# MINIPC_Board.net
KiCad netlist of a schematic drawn in EasyEDA Pro
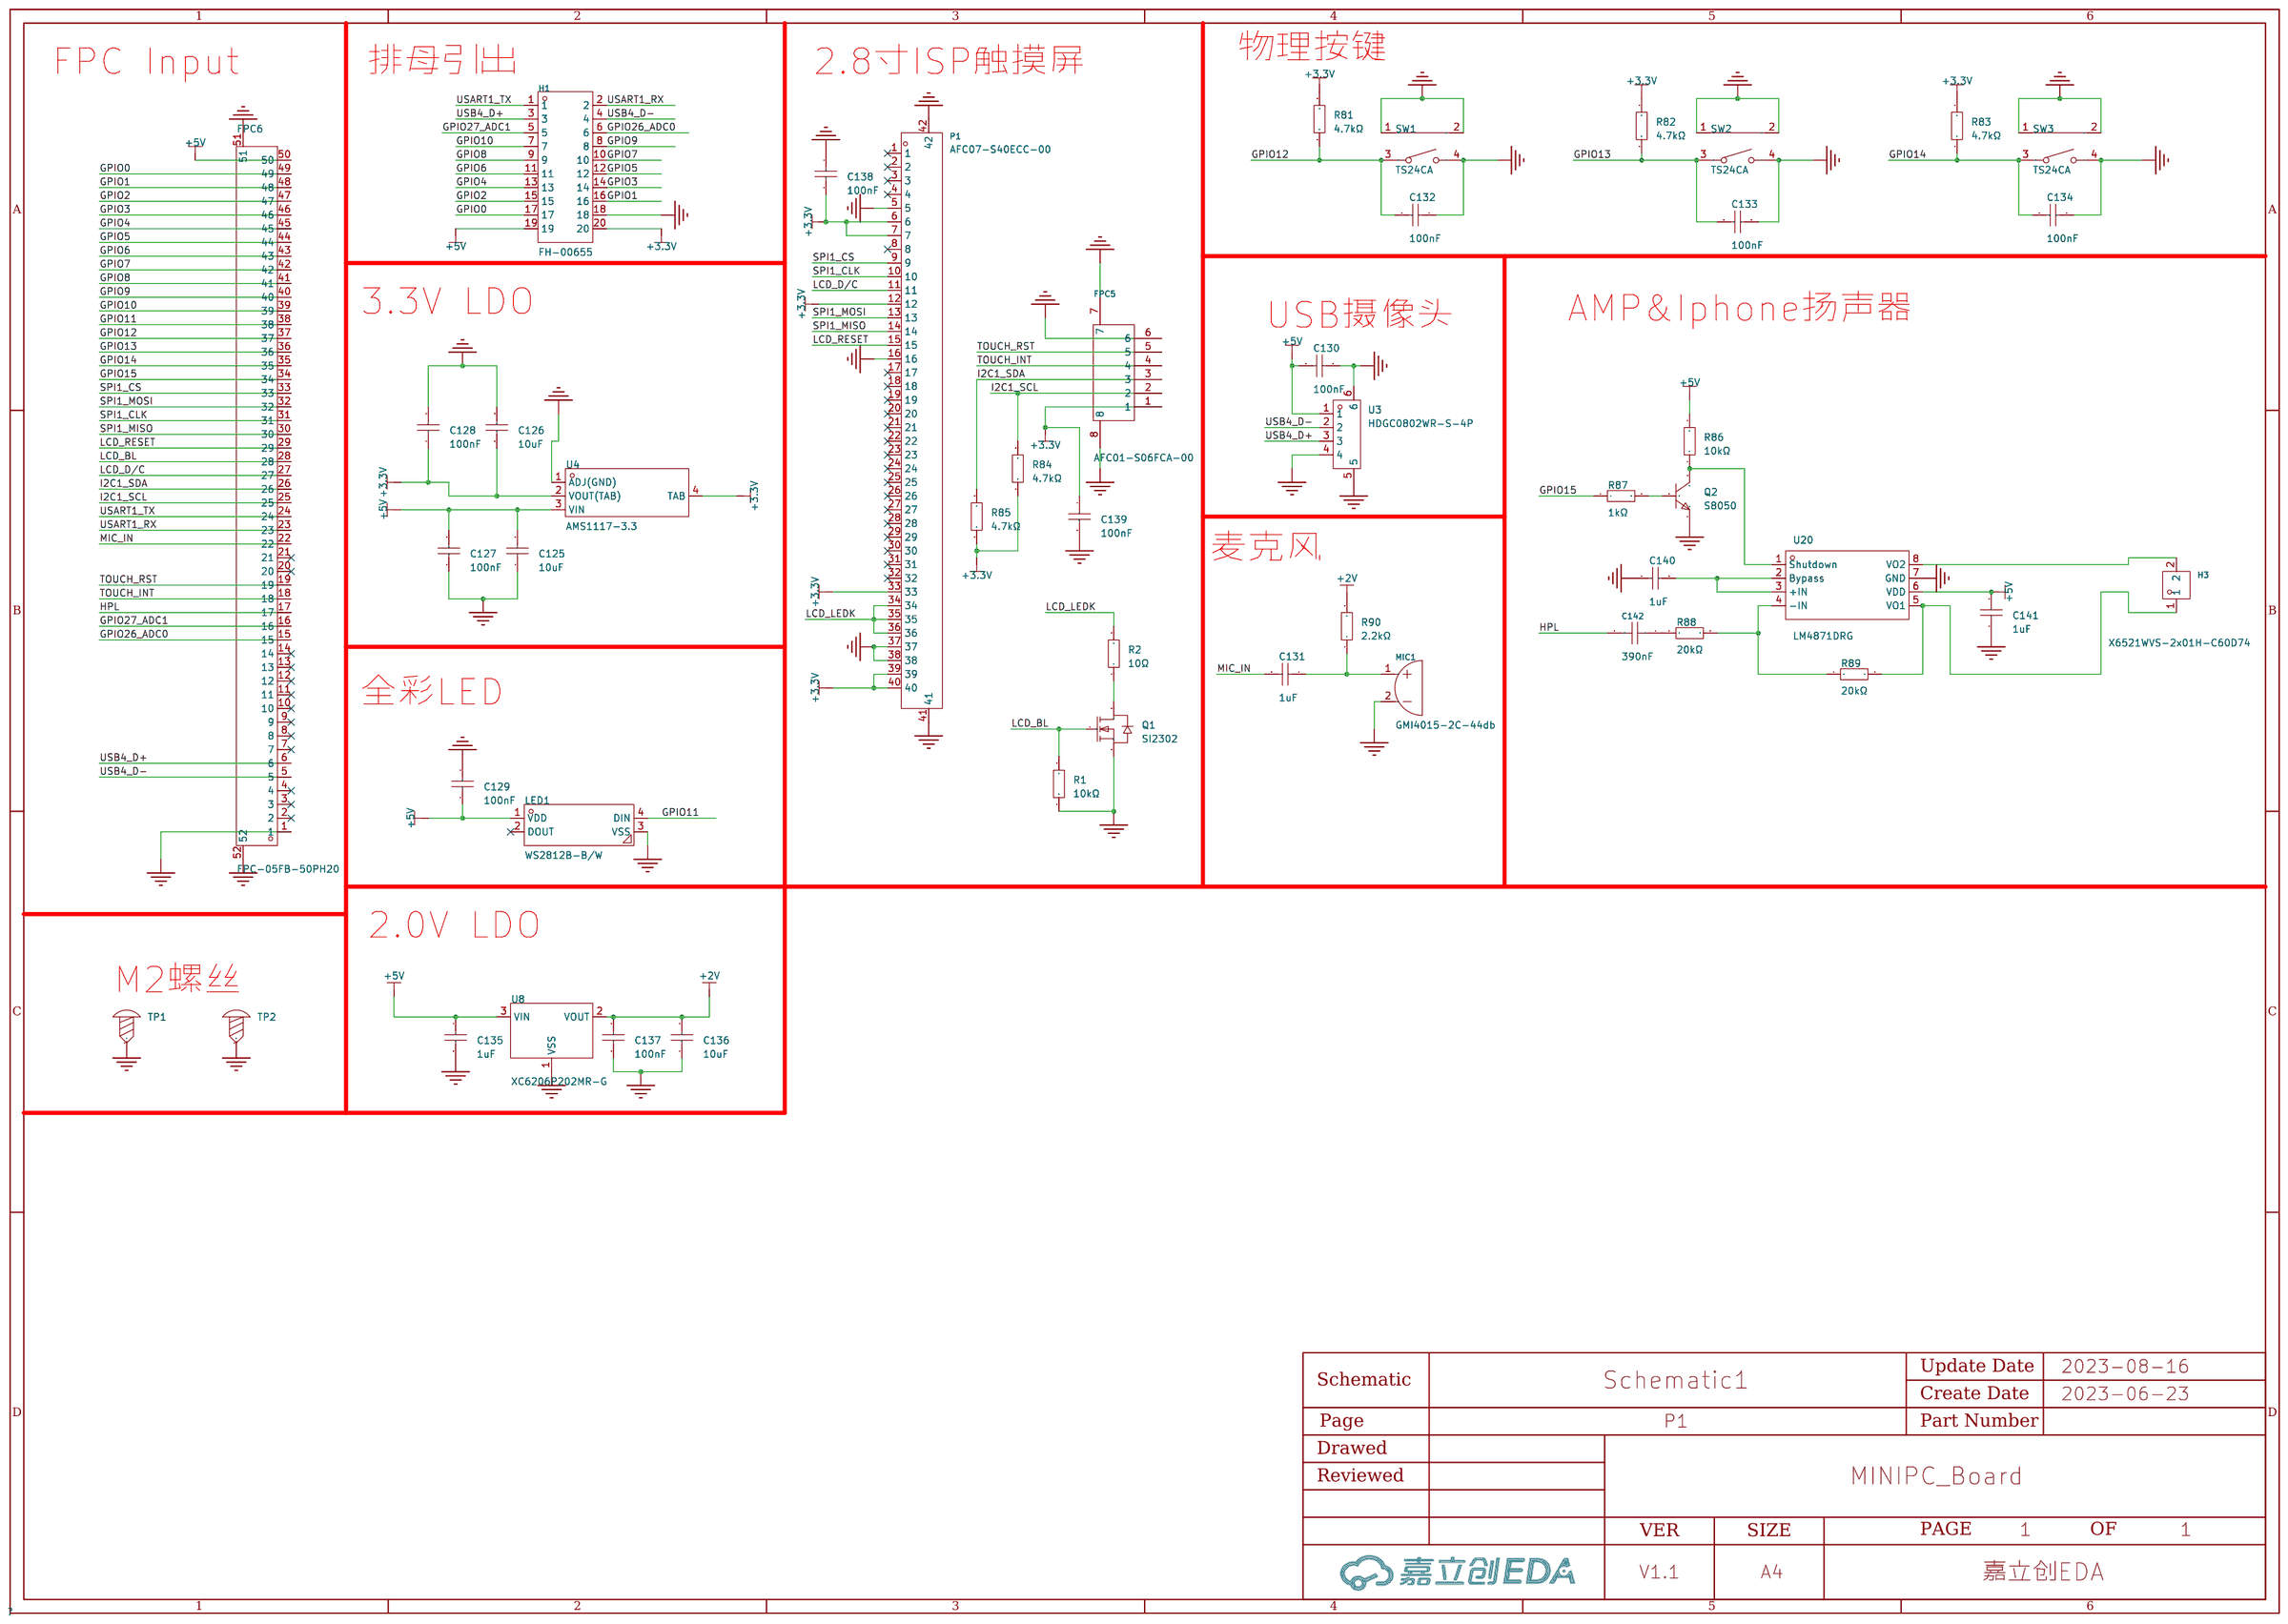
[diagram p0: schematic sheet]

(export (version "E")
  (design (tool "Eeschema 10.0.6"))
  (components
    (comp (ref "C125")
      (value "10uF")
      (footprint "easyedapro:C0805")
      (description "容值:10uF;精度:±10%;额定电压:25V;材质(温度系数):X5R;")
      (fields
        (field (name "Manufacturer Part") "CL21A106KAYNNNE")
        (field (name "Manufacturer") "SAMSUNG(三星)")
      )
      (libsource (lib "easyedapro") (part "CL21A106KAYNNNE"))
    )
    (comp (ref "C126")
      (value "10uF")
      (footprint "easyedapro:C0805")
      (description "容值:10uF;精度:±10%;额定电压:25V;材质(温度系数):X5R;")
      (fields
        (field (name "Manufacturer Part") "CL21A106KAYNNNE")
        (field (name "Manufacturer") "SAMSUNG(三星)")
      )
      (libsource (lib "easyedapro") (part "CL21A106KAYNNNE"))
    )
    (comp (ref "C127")
      (value "100nF")
      (footprint "easyedapro:C0805")
      (description "容值:100nF;精度:±10%;额定电压:50V;材质(温度系数):X7R;")
      (fields (field (name "Manufacturer Part") "0805B104K500NT") (field (name "Manufacturer") "FH(风华)"))
      (libsource (lib "easyedapro") (part "0805B104K500NT"))
    )
    (comp (ref "C128")
      (value "100nF")
      (footprint "easyedapro:C0805")
      (description "容值:100nF;精度:±10%;额定电压:50V;材质(温度系数):X7R;")
      (fields (field (name "Manufacturer Part") "0805B104K500NT") (field (name "Manufacturer") "FH(风华)"))
      (libsource (lib "easyedapro") (part "0805B104K500NT"))
    )
    (comp (ref "C129")
      (value "100nF")
      (footprint "easyedapro:C0805")
      (description "容值:100nF;精度:±10%;额定电压:50V;材质(温度系数):X7R;")
      (fields (field (name "Manufacturer Part") "0805B104K500NT") (field (name "Manufacturer") "FH(风华)"))
      (libsource (lib "easyedapro") (part "0805B104K500NT"))
    )
    (comp (ref "C130")
      (value "100nF")
      (footprint "easyedapro:C0805")
      (description "容值:100nF;精度:±10%;额定电压:50V;材质(温度系数):X7R;")
      (fields (field (name "Manufacturer Part") "0805B104K500NT") (field (name "Manufacturer") "FH(风华)"))
      (libsource (lib "easyedapro") (part "0805B104K500NT"))
    )
    (comp (ref "C131")
      (value "1uF")
      (footprint "easyedapro:C0805")
      (description "容值:1uF;精度:±10%;额定电压:50V;材质(温度系数):X7R;")
      (fields
        (field (name "Manufacturer Part") "CL21B105KBFNNNE")
        (field (name "Manufacturer") "SAMSUNG(三星)")
      )
      (libsource (lib "easyedapro") (part "CL21B105KBFNNNE"))
    )
    (comp (ref "C132")
      (value "100nF")
      (footprint "easyedapro:C0805")
      (description "容值:100nF;精度:±10%;额定电压:50V;材质(温度系数):X7R;")
      (fields (field (name "Manufacturer Part") "0805B104K500NT") (field (name "Manufacturer") "FH(风华)"))
      (libsource (lib "easyedapro") (part "0805B104K500NT"))
    )
    (comp (ref "C133")
      (value "100nF")
      (footprint "easyedapro:C0805")
      (description "容值:100nF;精度:±10%;额定电压:50V;材质(温度系数):X7R;")
      (fields (field (name "Manufacturer Part") "0805B104K500NT") (field (name "Manufacturer") "FH(风华)"))
      (libsource (lib "easyedapro") (part "0805B104K500NT"))
    )
    (comp (ref "C134")
      (value "100nF")
      (footprint "easyedapro:C0805")
      (description "容值:100nF;精度:±10%;额定电压:50V;材质(温度系数):X7R;")
      (fields (field (name "Manufacturer Part") "0805B104K500NT") (field (name "Manufacturer") "FH(风华)"))
      (libsource (lib "easyedapro") (part "0805B104K500NT"))
    )
    (comp (ref "C135")
      (value "1uF")
      (footprint "easyedapro:C0805")
      (description "容值:1uF;精度:±10%;额定电压:50V;材质(温度系数):X7R;")
      (fields
        (field (name "Manufacturer Part") "CL21B105KBFNNNE")
        (field (name "Manufacturer") "SAMSUNG(三星)")
      )
      (libsource (lib "easyedapro") (part "CL21B105KBFNNNE"))
    )
    (comp (ref "C136")
      (value "10uF")
      (footprint "easyedapro:C0805")
      (description "容值:10uF;精度:±10%;额定电压:25V;材质(温度系数):X5R;")
      (fields
        (field (name "Manufacturer Part") "CL21A106KAYNNNE")
        (field (name "Manufacturer") "SAMSUNG(三星)")
      )
      (libsource (lib "easyedapro") (part "CL21A106KAYNNNE"))
    )
    (comp (ref "C137")
      (value "100nF")
      (footprint "easyedapro:C0805")
      (description "容值:100nF;精度:±10%;额定电压:50V;材质(温度系数):X7R;")
      (fields (field (name "Manufacturer Part") "0805B104K500NT") (field (name "Manufacturer") "FH(风华)"))
      (libsource (lib "easyedapro") (part "0805B104K500NT"))
    )
    (comp (ref "C138")
      (value "100nF")
      (footprint "easyedapro:C0805")
      (description "容值:100nF;精度:±10%;额定电压:50V;材质(温度系数):X7R;")
      (fields (field (name "Manufacturer Part") "0805B104K500NT") (field (name "Manufacturer") "FH(风华)"))
      (libsource (lib "easyedapro") (part "0805B104K500NT"))
    )
    (comp (ref "C139")
      (value "100nF")
      (footprint "easyedapro:C0805")
      (description "容值:100nF;精度:±10%;额定电压:50V;材质(温度系数):X7R;")
      (fields (field (name "Manufacturer Part") "0805B104K500NT") (field (name "Manufacturer") "FH(风华)"))
      (libsource (lib "easyedapro") (part "0805B104K500NT"))
    )
    (comp (ref "C140")
      (value "1uF")
      (footprint "easyedapro:C0805")
      (description "容值:1uF;精度:±10%;额定电压:50V;材质(温度系数):X7R;")
      (fields
        (field (name "Manufacturer Part") "CL21B105KBFNNNE")
        (field (name "Manufacturer") "SAMSUNG(三星)")
      )
      (libsource (lib "easyedapro") (part "CL21B105KBFNNNE"))
    )
    (comp (ref "C141")
      (value "1uF")
      (footprint "easyedapro:C0805")
      (description "容值:1uF;精度:±10%;额定电压:50V;材质(温度系数):X7R;")
      (fields
        (field (name "Manufacturer Part") "CL21B105KBFNNNE")
        (field (name "Manufacturer") "SAMSUNG(三星)")
      )
      (libsource (lib "easyedapro") (part "CL21B105KBFNNNE"))
    )
    (comp (ref "C142")
      (value "390nF")
      (footprint "easyedapro:C0805")
      (description "容值:390nF;精度:±10%;额定电压:50V;材质(温度系数):X7R;")
      (fields (field (name "Manufacturer Part") "0805B394K500CT") (field (name "Manufacturer") "Walsin(华新科)"))
      (libsource (lib "easyedapro") (part "0805B394K500CT"))
    )
    (comp (ref "FPC5")
      (value "AFC01-S06FCA-00")
      (footprint "easyedapro:FPC-SMD_P0.50-6P_AFC01-S06FCA-00")
      (description "间距:0.5mm;触点数量:6;锁定特性:翻盖式;安装类型:卧贴;触点类型:下接;")
      (fields (field (name "Manufacturer") "JS(钜硕电子)"))
      (libsource (lib "easyedapro") (part "AFC01-S06FCA-00"))
    )
    (comp (ref "FPC6")
      (value "FPC-05FB-50PH20")
      (footprint "easyedapro:FPC-SMD_50P-P0.50_FPC-05FB-50PH20")
      (fields (field (name "Manufacturer") "XUNPU(讯普)"))
      (libsource (lib "easyedapro") (part "FPC-05FB-50PH20"))
    )
    (comp (ref "H1")
      (value "FH-00655")
      (footprint "easyedapro:HDR-SMD_20P-P2.54-V-F-R2-C10-S2.54-LS7.2-1")
      (fields (field (name "Manufacturer") "Liansheng(连盛)"))
      (libsource (lib "easyedapro") (part "FH-00655"))
    )
    (comp (ref "H3")
      (value "X6521WVS-2x01H-C60D74")
      (footprint "easyedapro:HDR-SMD_2P-P2.54-V-M-R2-C1-LS7.4")
      (fields (field (name "Manufacturer") "XKB Connectivity(中国星坤)"))
      (libsource (lib "easyedapro") (part "X6521WVS-2X01H-C60D74"))
    )
    (comp (ref "LED1")
      (value "WS2812B-B/W")
      (footprint "easyedapro:LED-SMD_4P-L5.0-W5.0-BL_TC5050RGB")
      (description "发光颜色:RGB三色;")
      (fields (field (name "Manufacturer") "worldsemi"))
      (libsource (lib "easyedapro") (part "WS2812B-B"))
    )
    (comp (ref "MIC1")
      (value "GMI4015-2C-44db")
      (footprint "easyedapro:MIC-SMD_BD4.0_GMI4015-2C-32DB")
      (fields (field (name "Manufacturer") "INGHAi(赢海)"))
      (libsource (lib "easyedapro") (part "GMI4015-2C-44DB"))
    )
    (comp (ref "P1")
      (value "AFC07-S40ECC-00")
      (footprint "easyedapro:CONN-SMD_AFC07-S40ECC-00")
      (description "间距:0.5mm;触点数量:40P;锁定特性:抽屉式;安装类型:卧贴;触点类型:上接;")
      (fields (field (name "Manufacturer") "JS(钜硕电子)"))
      (libsource (lib "easyedapro") (part "FPC 0.5MM 40P Pull type H2.0mm Pick up"))
    )
    (comp (ref "Q1")
      (value "SI2302")
      (footprint "easyedapro:SOT-23-3_L2.9-W1.5-P1.90-LS2.6-BL")
      (fields (field (name "Manufacturer") "TWGMC(台湾迪嘉)"))
      (libsource (lib "easyedapro") (part "SI2302_C727152"))
    )
    (comp (ref "Q2")
      (value "S8050")
      (footprint "easyedapro:SOT-23-3_L2.9-W1.6-P1.90-LS2.8-BR")
      (description "晶体管类型:NPN;集射极击穿电压(Vceo):25V;集电极电流(Ic):500mA;功率(Pd):300mW;直流电流增益(hFE@Ic,Vce):120@50mA,1V;")
      (fields (field (name "Manufacturer") "CJ(江苏长电/长晶)"))
      (libsource (lib "easyedapro") (part "S8050_C105433"))
    )
    (comp (ref "R1")
      (value "10kΩ")
      (footprint "easyedapro:R0805")
      (description "电阻类型:厚膜电阻;阻值:10kΩ;精度:±1%;功率:125mW;")
      (fields
        (field (name "Manufacturer Part") "0805W8F1002T5E")
        (field (name "Manufacturer") "UNI-ROYAL(厚声)")
      )
      (libsource (lib "easyedapro") (part "0805W8F1002T5E"))
    )
    (comp (ref "R2")
      (value "10Ω")
      (footprint "easyedapro:R0805_NEW")
      (description "电阻类型:厚膜电阻;阻值:10Ω;精度:±1%;功率:125mW;")
      (fields
        (field (name "Manufacturer Part") "0805W8F100JT5E")
        (field (name "Manufacturer") "UNI-ROYAL(厚声)")
      )
      (libsource (lib "easyedapro") (part "0805W8F100JT5E"))
    )
    (comp (ref "R81")
      (value "4.7kΩ")
      (footprint "easyedapro:R0805")
      (description "电阻类型:厚膜电阻;阻值:4.7kΩ;精度:±1%;功率:125mW;")
      (fields
        (field (name "Manufacturer Part") "0805W8F4701T5E")
        (field (name "Manufacturer") "UNI-ROYAL(厚声)")
      )
      (libsource (lib "easyedapro") (part "0805W8F4701T5E"))
    )
    (comp (ref "R82")
      (value "4.7kΩ")
      (footprint "easyedapro:R0805")
      (description "电阻类型:厚膜电阻;阻值:4.7kΩ;精度:±1%;功率:125mW;")
      (fields
        (field (name "Manufacturer Part") "0805W8F4701T5E")
        (field (name "Manufacturer") "UNI-ROYAL(厚声)")
      )
      (libsource (lib "easyedapro") (part "0805W8F4701T5E"))
    )
    (comp (ref "R83")
      (value "4.7kΩ")
      (footprint "easyedapro:R0805")
      (description "电阻类型:厚膜电阻;阻值:4.7kΩ;精度:±1%;功率:125mW;")
      (fields
        (field (name "Manufacturer Part") "0805W8F4701T5E")
        (field (name "Manufacturer") "UNI-ROYAL(厚声)")
      )
      (libsource (lib "easyedapro") (part "0805W8F4701T5E"))
    )
    (comp (ref "R84")
      (value "4.7kΩ")
      (footprint "easyedapro:R0805")
      (description "电阻类型:厚膜电阻;阻值:4.7kΩ;精度:±1%;功率:125mW;")
      (fields
        (field (name "Manufacturer Part") "0805W8F4701T5E")
        (field (name "Manufacturer") "UNI-ROYAL(厚声)")
      )
      (libsource (lib "easyedapro") (part "0805W8F4701T5E"))
    )
    (comp (ref "R85")
      (value "4.7kΩ")
      (footprint "easyedapro:R0805")
      (description "电阻类型:厚膜电阻;阻值:4.7kΩ;精度:±1%;功率:125mW;")
      (fields
        (field (name "Manufacturer Part") "0805W8F4701T5E")
        (field (name "Manufacturer") "UNI-ROYAL(厚声)")
      )
      (libsource (lib "easyedapro") (part "0805W8F4701T5E"))
    )
    (comp (ref "R86")
      (value "10kΩ")
      (footprint "easyedapro:R0805")
      (description "电阻类型:厚膜电阻;阻值:10kΩ;精度:±1%;功率:125mW;")
      (fields
        (field (name "Manufacturer Part") "0805W8F1002T5E")
        (field (name "Manufacturer") "UNI-ROYAL(厚声)")
      )
      (libsource (lib "easyedapro") (part "0805W8F1002T5E"))
    )
    (comp (ref "R87")
      (value "1kΩ")
      (footprint "easyedapro:R0805")
      (description "电阻类型:厚膜电阻;阻值:1kΩ;精度:±1%;功率:125mW;")
      (fields
        (field (name "Manufacturer Part") "0805W8F1001T5E")
        (field (name "Manufacturer") "UNI-ROYAL(厚声)")
      )
      (libsource (lib "easyedapro") (part "0805W8F1001T5E"))
    )
    (comp (ref "R88")
      (value "20kΩ")
      (footprint "easyedapro:R0805")
      (description "电阻类型:厚膜电阻;阻值:20kΩ;精度:±1%;功率:125mW;")
      (fields
        (field (name "Manufacturer Part") "0805W8F2002T5E")
        (field (name "Manufacturer") "UNI-ROYAL(厚声)")
      )
      (libsource (lib "easyedapro") (part "0805W8F2002T5E"))
    )
    (comp (ref "R89")
      (value "20kΩ")
      (footprint "easyedapro:R0805")
      (description "电阻类型:厚膜电阻;阻值:20kΩ;精度:±1%;功率:125mW;")
      (fields
        (field (name "Manufacturer Part") "0805W8F2002T5E")
        (field (name "Manufacturer") "UNI-ROYAL(厚声)")
      )
      (libsource (lib "easyedapro") (part "0805W8F2002T5E"))
    )
    (comp (ref "R90")
      (value "2.2kΩ")
      (footprint "easyedapro:R0805")
      (description "电阻类型:厚膜电阻;阻值:2.2kΩ;精度:±1%;功率:125mW;")
      (fields
        (field (name "Manufacturer Part") "0805W8F2201T5E")
        (field (name "Manufacturer") "UNI-ROYAL(厚声)")
      )
      (libsource (lib "easyedapro") (part "0805W8F2201T5E"))
    )
    (comp (ref "SW1")
      (value "TS24CA")
      (footprint "easyedapro:SW-SMD_TS24CA")
      (description "触点电流:50mA;额定电压(DC):12V;电路结构:单刀单掷;安装方式:卧贴;带灯:-;机械寿命:-;")
      (fields (field (name "Manufacturer") "SHOU HAN(首韩)"))
      (libsource (lib "easyedapro") (part "TS24CA"))
    )
    (comp (ref "SW2")
      (value "TS24CA")
      (footprint "easyedapro:SW-SMD_TS24CA")
      (description "触点电流:50mA;额定电压(DC):12V;电路结构:单刀单掷;安装方式:卧贴;带灯:-;机械寿命:-;")
      (fields (field (name "Manufacturer") "SHOU HAN(首韩)"))
      (libsource (lib "easyedapro") (part "TS24CA"))
    )
    (comp (ref "SW3")
      (value "TS24CA")
      (footprint "easyedapro:SW-SMD_TS24CA")
      (description "触点电流:50mA;额定电压(DC):12V;电路结构:单刀单掷;安装方式:卧贴;带灯:-;机械寿命:-;")
      (fields (field (name "Manufacturer") "SHOU HAN(首韩)"))
      (libsource (lib "easyedapro") (part "TS24CA"))
    )
    (comp (ref "TP1") (value "~") (footprint "easyedapro:M2螺丝") (libsource (lib "easyedapro") (part "螺丝孔")))
    (comp (ref "TP2") (value "~") (footprint "easyedapro:M2螺丝") (libsource (lib "easyedapro") (part "螺丝孔")))
    (comp (ref "U3")
      (value "HDGC0802WR-S-4P")
      (footprint "easyedapro:CONN-SMD_4P-P0.80_HDGC_HDGC0802WR-S-4P")
      (description "间距:0.8mm;插针结构:1x4P;排数:1;每排PIN数:4;公母:公型插针;安装方式:卧贴;工作温度范围:-25°C~+85°C;")
      (fields (field (name "Manufacturer") "HDGC(华德共创)"))
      (libsource (lib "easyedapro") (part "HDGC0802WR-S-4P"))
    )
    (comp (ref "U4")
      (value "AMS1117-3.3")
      (footprint "easyedapro:SOT-223-4_L6.5-W3.5-P2.30-LS7.0-BR")
      (description "输出类型:固定;输出极性:正;最大输入电压:18V;输出电压:3.3V;输出电流:1A;电源纹波抑制比(PSRR):60dB@(120Hz);")
      (fields (field (name "Manufacturer") "UMW(广东友台半导体)"))
      (libsource (lib "easyedapro") (part "AMS1117-3.3_C347222"))
    )
    (comp (ref "U8")
      (value "XC6206P202MR-G")
      (footprint "easyedapro:SOT-23-3_L3.0-W1.7-P0.95-LS2.9-BR")
      (description "输出类型:固定;输出极性:正;最大输入电压:8V;输出电压:3V;输出电流:300mA;")
      (fields (field (name "Manufacturer") "TOREX(特瑞仕)"))
      (libsource (lib "easyedapro") (part "XC6206P302MR_C5148691"))
    )
    (comp (ref "U20")
      (value "LM4871DRG")
      (footprint "easyedapro:SOP-8_L4.9-W3.9-P1.27-LS6.0-BL")
      (fields (field (name "Manufacturer") "HGC(深圳汉芯)"))
      (libsource (lib "easyedapro") (part "LM4871DRG"))
    )
  )
  (nets
    (net (code "1") (name "+2V") (class "Default")
      (node (ref "C136") (pin "2") (pinfunction "2_2") (pintype "input"))
      (node (ref "C137") (pin "2") (pinfunction "2_2") (pintype "input"))
      (node (ref "R90") (pin "2") (pinfunction "2_2") (pintype "input"))
      (node (ref "U8") (pin "2") (pinfunction "VOUT_2") (pintype "input"))
    )
    (net (code "2") (name "+3.3V") (class "Default")
      (node (ref "C126") (pin "1") (pinfunction "1_1") (pintype "input"))
      (node (ref "C128") (pin "1") (pinfunction "1_1") (pintype "input"))
      (node (ref "C138") (pin "2") (pinfunction "2_2") (pintype "input"))
      (node (ref "C139") (pin "1") (pinfunction "1_1") (pintype "input"))
      (node (ref "FPC5") (pin "1") (pinfunction "1_1") (pintype "input"))
      (node (ref "H1") (pin "20") (pinfunction "20_20") (pintype "input"))
      (node (ref "P1") (pin "12") (pinfunction "12_12") (pintype "input"))
      (node (ref "P1") (pin "33") (pinfunction "33_33") (pintype "input"))
      (node (ref "P1") (pin "39") (pinfunction "39_39") (pintype "input"))
      (node (ref "P1") (pin "40") (pinfunction "40_40") (pintype "input"))
      (node (ref "P1") (pin "6") (pinfunction "6_6") (pintype "input"))
      (node (ref "P1") (pin "7") (pinfunction "7_7") (pintype "input"))
      (node (ref "R81") (pin "2") (pinfunction "2_2") (pintype "input"))
      (node (ref "R82") (pin "2") (pinfunction "2_2") (pintype "input"))
      (node (ref "R83") (pin "2") (pinfunction "2_2") (pintype "input"))
      (node (ref "R84") (pin "1") (pinfunction "1_1") (pintype "input"))
      (node (ref "R85") (pin "1") (pinfunction "1_1") (pintype "input"))
      (node (ref "U4") (pin "2") (pinfunction "VOUT(TAB)_2") (pintype "input"))
      (node (ref "U4") (pin "4") (pinfunction "TAB_4") (pintype "input"))
    )
    (net (code "3") (name "+5V") (class "Default")
      (node (ref "C125") (pin "2") (pinfunction "2_2") (pintype "input"))
      (node (ref "C127") (pin "2") (pinfunction "2_2") (pintype "input"))
      (node (ref "C129") (pin "1") (pinfunction "1_1") (pintype "input"))
      (node (ref "C130") (pin "2") (pinfunction "2_2") (pintype "input"))
      (node (ref "C135") (pin "1") (pinfunction "1_1") (pintype "input"))
      (node (ref "C141") (pin "2") (pinfunction "2_2") (pintype "input"))
      (node (ref "FPC6") (pin "50") (pinfunction "50_50") (pintype "input"))
      (node (ref "H1") (pin "19") (pinfunction "19_19") (pintype "input"))
      (node (ref "LED1") (pin "1") (pinfunction "VDD_1") (pintype "input"))
      (node (ref "R86") (pin "2") (pinfunction "2_2") (pintype "input"))
      (node (ref "U20") (pin "6") (pinfunction "VDD_6") (pintype "input"))
      (node (ref "U3") (pin "1") (pinfunction "1_1") (pintype "input"))
      (node (ref "U4") (pin "3") (pinfunction "VIN_3") (pintype "input"))
      (node (ref "U8") (pin "3") (pinfunction "VIN_3") (pintype "input"))
    )
    (net (code "4") (name "/GPIO0") (class "Default")
      (node (ref "FPC6") (pin "49") (pinfunction "49_49") (pintype "input"))
      (node (ref "H1") (pin "17") (pinfunction "17_17") (pintype "input"))
    )
    (net (code "5") (name "/GPIO1") (class "Default")
      (node (ref "FPC6") (pin "48") (pinfunction "48_48") (pintype "input"))
      (node (ref "H1") (pin "16") (pinfunction "16_16") (pintype "input"))
    )
    (net (code "6") (name "/GPIO2") (class "Default")
      (node (ref "FPC6") (pin "47") (pinfunction "47_47") (pintype "input"))
      (node (ref "H1") (pin "15") (pinfunction "15_15") (pintype "input"))
    )
    (net (code "7") (name "/GPIO3") (class "Default")
      (node (ref "FPC6") (pin "46") (pinfunction "46_46") (pintype "input"))
      (node (ref "H1") (pin "14") (pinfunction "14_14") (pintype "input"))
    )
    (net (code "8") (name "/GPIO4") (class "Default")
      (node (ref "FPC6") (pin "45") (pinfunction "45_45") (pintype "input"))
      (node (ref "H1") (pin "13") (pinfunction "13_13") (pintype "input"))
    )
    (net (code "9") (name "/GPIO5") (class "Default")
      (node (ref "FPC6") (pin "44") (pinfunction "44_44") (pintype "input"))
      (node (ref "H1") (pin "12") (pinfunction "12_12") (pintype "input"))
    )
    (net (code "10") (name "/GPIO6") (class "Default")
      (node (ref "FPC6") (pin "43") (pinfunction "43_43") (pintype "input"))
      (node (ref "H1") (pin "11") (pinfunction "11_11") (pintype "input"))
    )
    (net (code "11") (name "/GPIO7") (class "Default")
      (node (ref "FPC6") (pin "42") (pinfunction "42_42") (pintype "input"))
      (node (ref "H1") (pin "10") (pinfunction "10_10") (pintype "input"))
    )
    (net (code "12") (name "/GPIO8") (class "Default")
      (node (ref "FPC6") (pin "41") (pinfunction "41_41") (pintype "input"))
      (node (ref "H1") (pin "9") (pinfunction "9_9") (pintype "input"))
    )
    (net (code "13") (name "/GPIO9") (class "Default")
      (node (ref "FPC6") (pin "40") (pinfunction "40_40") (pintype "input"))
      (node (ref "H1") (pin "8") (pinfunction "8_8") (pintype "input"))
    )
    (net (code "14") (name "/GPIO10") (class "Default")
      (node (ref "FPC6") (pin "39") (pinfunction "39_39") (pintype "input"))
      (node (ref "H1") (pin "7") (pinfunction "7_7") (pintype "input"))
    )
    (net (code "15") (name "/GPIO11") (class "Default")
      (node (ref "FPC6") (pin "38") (pinfunction "38_38") (pintype "input"))
      (node (ref "LED1") (pin "4") (pinfunction "DIN_4") (pintype "input"))
    )
    (net (code "16") (name "/GPIO12") (class "Default")
      (node (ref "C132") (pin "2") (pinfunction "2_2") (pintype "input"))
      (node (ref "FPC6") (pin "37") (pinfunction "37_37") (pintype "input"))
      (node (ref "R81") (pin "1") (pinfunction "1_1") (pintype "input"))
      (node (ref "SW1") (pin "3") (pinfunction "3_3") (pintype "input"))
    )
    (net (code "17") (name "/GPIO13") (class "Default")
      (node (ref "C133") (pin "2") (pinfunction "2_2") (pintype "input"))
      (node (ref "FPC6") (pin "36") (pinfunction "36_36") (pintype "input"))
      (node (ref "R82") (pin "1") (pinfunction "1_1") (pintype "input"))
      (node (ref "SW2") (pin "3") (pinfunction "3_3") (pintype "input"))
    )
    (net (code "18") (name "/GPIO14") (class "Default")
      (node (ref "C134") (pin "2") (pinfunction "2_2") (pintype "input"))
      (node (ref "FPC6") (pin "35") (pinfunction "35_35") (pintype "input"))
      (node (ref "R83") (pin "1") (pinfunction "1_1") (pintype "input"))
      (node (ref "SW3") (pin "3") (pinfunction "3_3") (pintype "input"))
    )
    (net (code "19") (name "/GPIO15") (class "Default")
      (node (ref "FPC6") (pin "34") (pinfunction "34_34") (pintype "input"))
      (node (ref "R87") (pin "1") (pinfunction "1_1") (pintype "input"))
    )
    (net (code "20") (name "/GPIO26_ADC0") (class "Default")
      (node (ref "FPC6") (pin "15") (pinfunction "15_15") (pintype "input"))
      (node (ref "H1") (pin "6") (pinfunction "6_6") (pintype "input"))
    )
    (net (code "21") (name "/GPIO27_ADC1") (class "Default")
      (node (ref "FPC6") (pin "16") (pinfunction "16_16") (pintype "input"))
      (node (ref "H1") (pin "5") (pinfunction "5_5") (pintype "input"))
    )
    (net (code "22") (name "/HPL") (class "Default")
      (node (ref "C142") (pin "2") (pinfunction "2_2") (pintype "input"))
      (node (ref "FPC6") (pin "17") (pinfunction "17_17") (pintype "input"))
    )
    (net (code "23") (name "/I2C1_SCL") (class "Default")
      (node (ref "FPC5") (pin "2") (pinfunction "2_2") (pintype "input"))
      (node (ref "FPC6") (pin "25") (pinfunction "25_25") (pintype "input"))
      (node (ref "R84") (pin "2") (pinfunction "2_2") (pintype "input"))
    )
    (net (code "24") (name "/I2C1_SDA") (class "Default")
      (node (ref "FPC5") (pin "3") (pinfunction "3_3") (pintype "input"))
      (node (ref "FPC6") (pin "26") (pinfunction "26_26") (pintype "input"))
      (node (ref "R85") (pin "2") (pinfunction "2_2") (pintype "input"))
    )
    (net (code "25") (name "/LCD_BL") (class "Default")
      (node (ref "FPC6") (pin "28") (pinfunction "28_28") (pintype "input"))
      (node (ref "Q1") (pin "1") (pinfunction "G_1") (pintype "input"))
      (node (ref "R1") (pin "2") (pinfunction "2_2") (pintype "input"))
    )
    (net (code "26") (name "/LCD_D{slash}C") (class "Default")
      (node (ref "FPC6") (pin "27") (pinfunction "27_27") (pintype "input"))
      (node (ref "P1") (pin "11") (pinfunction "11_11") (pintype "input"))
    )
    (net (code "27") (name "/LCD_LEDK") (class "Default")
      (node (ref "P1") (pin "34") (pinfunction "34_34") (pintype "input"))
      (node (ref "P1") (pin "35") (pinfunction "35_35") (pintype "input"))
      (node (ref "P1") (pin "36") (pinfunction "36_36") (pintype "input"))
      (node (ref "R2") (pin "2") (pinfunction "2_2") (pintype "input"))
    )
    (net (code "28") (name "/LCD_RESET") (class "Default")
      (node (ref "FPC6") (pin "29") (pinfunction "29_29") (pintype "input"))
      (node (ref "P1") (pin "15") (pinfunction "15_15") (pintype "input"))
    )
    (net (code "29") (name "/MIC_IN") (class "Default")
      (node (ref "C131") (pin "2") (pinfunction "2_2") (pintype "input"))
      (node (ref "FPC6") (pin "22") (pinfunction "22_22") (pintype "input"))
    )
    (net (code "30") (name "/SPI1_CLK") (class "Default")
      (node (ref "FPC6") (pin "31") (pinfunction "31_31") (pintype "input"))
      (node (ref "P1") (pin "10") (pinfunction "10_10") (pintype "input"))
    )
    (net (code "31") (name "/SPI1_CS") (class "Default")
      (node (ref "FPC6") (pin "33") (pinfunction "33_33") (pintype "input"))
      (node (ref "P1") (pin "9") (pinfunction "9_9") (pintype "input"))
    )
    (net (code "32") (name "/SPI1_MISO") (class "Default")
      (node (ref "FPC6") (pin "30") (pinfunction "30_30") (pintype "input"))
      (node (ref "P1") (pin "14") (pinfunction "14_14") (pintype "input"))
    )
    (net (code "33") (name "/SPI1_MOSI") (class "Default")
      (node (ref "FPC6") (pin "32") (pinfunction "32_32") (pintype "input"))
      (node (ref "P1") (pin "13") (pinfunction "13_13") (pintype "input"))
    )
    (net (code "34") (name "/TOUCH_INT") (class "Default")
      (node (ref "FPC5") (pin "4") (pinfunction "4_4") (pintype "input"))
      (node (ref "FPC6") (pin "18") (pinfunction "18_18") (pintype "input"))
    )
    (net (code "35") (name "/TOUCH_RST") (class "Default")
      (node (ref "FPC5") (pin "5") (pinfunction "5_5") (pintype "input"))
      (node (ref "FPC6") (pin "19") (pinfunction "19_19") (pintype "input"))
    )
    (net (code "36") (name "/USART1_RX") (class "Default")
      (node (ref "FPC6") (pin "23") (pinfunction "23_23") (pintype "input"))
      (node (ref "H1") (pin "2") (pinfunction "2_2") (pintype "input"))
    )
    (net (code "37") (name "/USART1_TX") (class "Default")
      (node (ref "FPC6") (pin "24") (pinfunction "24_24") (pintype "input"))
      (node (ref "H1") (pin "1") (pinfunction "1_1") (pintype "input"))
    )
    (net (code "38") (name "/USB4_D+") (class "Default")
      (node (ref "FPC6") (pin "6") (pinfunction "6_6") (pintype "input"))
      (node (ref "H1") (pin "3") (pinfunction "3_3") (pintype "input"))
      (node (ref "U3") (pin "3") (pinfunction "3_3") (pintype "input"))
    )
    (net (code "39") (name "/USB4_D-") (class "Default")
      (node (ref "FPC6") (pin "5") (pinfunction "5_5") (pintype "input"))
      (node (ref "H1") (pin "4") (pinfunction "4_4") (pintype "input"))
      (node (ref "U3") (pin "2") (pinfunction "2_2") (pintype "input"))
    )
    (net (code "40") (name "GND") (class "Default")
      (node (ref "C125") (pin "1") (pinfunction "1_1") (pintype "input"))
      (node (ref "C126") (pin "2") (pinfunction "2_2") (pintype "input"))
      (node (ref "C127") (pin "1") (pinfunction "1_1") (pintype "input"))
      (node (ref "C128") (pin "2") (pinfunction "2_2") (pintype "input"))
      (node (ref "C129") (pin "2") (pinfunction "2_2") (pintype "input"))
      (node (ref "C130") (pin "1") (pinfunction "1_1") (pintype "input"))
      (node (ref "C132") (pin "1") (pinfunction "1_1") (pintype "input"))
      (node (ref "C133") (pin "1") (pinfunction "1_1") (pintype "input"))
      (node (ref "C134") (pin "1") (pinfunction "1_1") (pintype "input"))
      (node (ref "C135") (pin "2") (pinfunction "2_2") (pintype "input"))
      (node (ref "C136") (pin "1") (pinfunction "1_1") (pintype "input"))
      (node (ref "C137") (pin "1") (pinfunction "1_1") (pintype "input"))
      (node (ref "C138") (pin "1") (pinfunction "1_1") (pintype "input"))
      (node (ref "C139") (pin "2") (pinfunction "2_2") (pintype "input"))
      (node (ref "C140") (pin "1") (pinfunction "1_1") (pintype "input"))
      (node (ref "C141") (pin "1") (pinfunction "1_1") (pintype "input"))
      (node (ref "FPC5") (pin "6") (pinfunction "6_6") (pintype "input"))
      (node (ref "FPC5") (pin "7") (pinfunction "7_7") (pintype "input"))
      (node (ref "FPC5") (pin "8") (pinfunction "8_8") (pintype "input"))
      (node (ref "FPC6") (pin "1") (pinfunction "1_1") (pintype "input"))
      (node (ref "FPC6") (pin "51") (pinfunction "51_51") (pintype "input"))
      (node (ref "FPC6") (pin "52") (pinfunction "52_52") (pintype "input"))
      (node (ref "H1") (pin "18") (pinfunction "18_18") (pintype "input"))
      (node (ref "LED1") (pin "3") (pinfunction "VSS_3") (pintype "input"))
      (node (ref "MIC1") (pin "2") (pinfunction "-_2") (pintype "input"))
      (node (ref "P1") (pin "16") (pinfunction "16_16") (pintype "input"))
      (node (ref "P1") (pin "37") (pinfunction "37_37") (pintype "input"))
      (node (ref "P1") (pin "38") (pinfunction "38_38") (pintype "input"))
      (node (ref "P1") (pin "41") (pinfunction "41_41") (pintype "input"))
      (node (ref "P1") (pin "42") (pinfunction "42_42") (pintype "input"))
      (node (ref "P1") (pin "5") (pinfunction "5_5") (pintype "input"))
      (node (ref "Q1") (pin "2") (pinfunction "S_2") (pintype "input"))
      (node (ref "Q2") (pin "2") (pinfunction "2_2") (pintype "input"))
      (node (ref "R1") (pin "1") (pinfunction "1_1") (pintype "input"))
      (node (ref "SW1") (pin "1") (pinfunction "1_1") (pintype "input"))
      (node (ref "SW1") (pin "2") (pinfunction "2_2") (pintype "input"))
      (node (ref "SW1") (pin "4") (pinfunction "4_4") (pintype "input"))
      (node (ref "SW2") (pin "1") (pinfunction "1_1") (pintype "input"))
      (node (ref "SW2") (pin "2") (pinfunction "2_2") (pintype "input"))
      (node (ref "SW2") (pin "4") (pinfunction "4_4") (pintype "input"))
      (node (ref "SW3") (pin "1") (pinfunction "1_1") (pintype "input"))
      (node (ref "SW3") (pin "2") (pinfunction "2_2") (pintype "input"))
      (node (ref "SW3") (pin "4") (pinfunction "4_4") (pintype "input"))
      (node (ref "TP1") (pin "1") (pinfunction "1_1") (pintype "input"))
      (node (ref "TP2") (pin "1") (pinfunction "1_1") (pintype "input"))
      (node (ref "U20") (pin "7") (pinfunction "GND_7") (pintype "input"))
      (node (ref "U3") (pin "4") (pinfunction "4_4") (pintype "input"))
      (node (ref "U3") (pin "5") (pinfunction "5_5") (pintype "input"))
      (node (ref "U3") (pin "6") (pinfunction "6_6") (pintype "input"))
      (node (ref "U4") (pin "1") (pinfunction "ADJ(GND)_1") (pintype "input"))
      (node (ref "U8") (pin "1") (pinfunction "VSS_1") (pintype "input"))
    )
    (net (code "41") (name "Net-(C142-Pad1)") (class "Default")
      (node (ref "C142") (pin "1") (pinfunction "1_1") (pintype "input"))
      (node (ref "R88") (pin "1") (pinfunction "1_1") (pintype "input"))
    )
    (net (code "42") (name "Net-(MIC1-+)") (class "Default")
      (node (ref "C131") (pin "1") (pinfunction "1_1") (pintype "input"))
      (node (ref "MIC1") (pin "1") (pinfunction "+_1") (pintype "input"))
      (node (ref "R90") (pin "1") (pinfunction "1_1") (pintype "input"))
    )
    (net (code "43") (name "Net-(Q1-D)") (class "Default")
      (node (ref "Q1") (pin "3") (pinfunction "D_3") (pintype "input"))
      (node (ref "R2") (pin "1") (pinfunction "1_1") (pintype "input"))
    )
    (net (code "44") (name "Net-(Q2-Pad1)") (class "Default")
      (node (ref "Q2") (pin "1") (pinfunction "1_1") (pintype "input"))
      (node (ref "R87") (pin "2") (pinfunction "2_2") (pintype "input"))
    )
    (net (code "45") (name "Net-(U20-+IN)") (class "Default")
      (node (ref "C140") (pin "2") (pinfunction "2_2") (pintype "input"))
      (node (ref "U20") (pin "2") (pinfunction "Bypass_2") (pintype "input"))
      (node (ref "U20") (pin "3") (pinfunction "+IN_3") (pintype "input"))
    )
    (net (code "46") (name "Net-(U20--IN)") (class "Default")
      (node (ref "R88") (pin "2") (pinfunction "2_2") (pintype "input"))
      (node (ref "R89") (pin "1") (pinfunction "1_1") (pintype "input"))
      (node (ref "U20") (pin "4") (pinfunction "-IN_4") (pintype "input"))
    )
    (net (code "47") (name "Net-(U20-Shutdown)") (class "Default")
      (node (ref "Q2") (pin "3") (pinfunction "3_3") (pintype "input"))
      (node (ref "R86") (pin "1") (pinfunction "1_1") (pintype "input"))
      (node (ref "U20") (pin "1") (pinfunction "Shutdown_1") (pintype "input"))
    )
    (net (code "48") (name "Net-(U20-VO1)") (class "Default")
      (node (ref "H3") (pin "1") (pinfunction "1_1") (pintype "input"))
      (node (ref "R89") (pin "2") (pinfunction "2_2") (pintype "input"))
      (node (ref "U20") (pin "5") (pinfunction "VO1_5") (pintype "input"))
    )
    (net (code "49") (name "Net-(U20-VO2)") (class "Default")
      (node (ref "H3") (pin "2") (pinfunction "2_2") (pintype "input"))
      (node (ref "U20") (pin "8") (pinfunction "VO2_8") (pintype "input"))
    )
    (net (code "50") (name "unconnected-(FPC6-Pad2)") (class "Default")
      (node (ref "FPC6") (pin "2") (pinfunction "2_2") (pintype "input+no_connect"))
    )
    (net (code "51") (name "unconnected-(FPC6-Pad3)") (class "Default")
      (node (ref "FPC6") (pin "3") (pinfunction "3_3") (pintype "input+no_connect"))
    )
    (net (code "52") (name "unconnected-(FPC6-Pad4)") (class "Default")
      (node (ref "FPC6") (pin "4") (pinfunction "4_4") (pintype "input+no_connect"))
    )
    (net (code "53") (name "unconnected-(FPC6-Pad7)") (class "Default")
      (node (ref "FPC6") (pin "7") (pinfunction "7_7") (pintype "input+no_connect"))
    )
    (net (code "54") (name "unconnected-(FPC6-Pad8)") (class "Default")
      (node (ref "FPC6") (pin "8") (pinfunction "8_8") (pintype "input+no_connect"))
    )
    (net (code "55") (name "unconnected-(FPC6-Pad9)") (class "Default")
      (node (ref "FPC6") (pin "9") (pinfunction "9_9") (pintype "input+no_connect"))
    )
    (net (code "56") (name "unconnected-(FPC6-Pad10)") (class "Default")
      (node (ref "FPC6") (pin "10") (pinfunction "10_10") (pintype "input+no_connect"))
    )
    (net (code "57") (name "unconnected-(FPC6-Pad11)") (class "Default")
      (node (ref "FPC6") (pin "11") (pinfunction "11_11") (pintype "input+no_connect"))
    )
    (net (code "58") (name "unconnected-(FPC6-Pad12)") (class "Default")
      (node (ref "FPC6") (pin "12") (pinfunction "12_12") (pintype "input+no_connect"))
    )
    (net (code "59") (name "unconnected-(FPC6-Pad13)") (class "Default")
      (node (ref "FPC6") (pin "13") (pinfunction "13_13") (pintype "input+no_connect"))
    )
    (net (code "60") (name "unconnected-(FPC6-Pad14)") (class "Default")
      (node (ref "FPC6") (pin "14") (pinfunction "14_14") (pintype "input+no_connect"))
    )
    (net (code "61") (name "unconnected-(FPC6-Pad20)") (class "Default")
      (node (ref "FPC6") (pin "20") (pinfunction "20_20") (pintype "input+no_connect"))
    )
    (net (code "62") (name "unconnected-(FPC6-Pad21)") (class "Default")
      (node (ref "FPC6") (pin "21") (pinfunction "21_21") (pintype "input+no_connect"))
    )
    (net (code "63") (name "unconnected-(LED1-DOUT-Pad2)") (class "Default")
      (node (ref "LED1") (pin "2") (pinfunction "DOUT_2") (pintype "input+no_connect"))
    )
    (net (code "64") (name "unconnected-(P1-Pad1)") (class "Default")
      (node (ref "P1") (pin "1") (pinfunction "1_1") (pintype "input+no_connect"))
    )
    (net (code "65") (name "unconnected-(P1-Pad2)") (class "Default")
      (node (ref "P1") (pin "2") (pinfunction "2_2") (pintype "input+no_connect"))
    )
    (net (code "66") (name "unconnected-(P1-Pad3)") (class "Default")
      (node (ref "P1") (pin "3") (pinfunction "3_3") (pintype "input+no_connect"))
    )
    (net (code "67") (name "unconnected-(P1-Pad4)") (class "Default")
      (node (ref "P1") (pin "4") (pinfunction "4_4") (pintype "input+no_connect"))
    )
    (net (code "68") (name "unconnected-(P1-Pad8)") (class "Default")
      (node (ref "P1") (pin "8") (pinfunction "8_8") (pintype "input+no_connect"))
    )
    (net (code "69") (name "unconnected-(P1-Pad17)") (class "Default")
      (node (ref "P1") (pin "17") (pinfunction "17_17") (pintype "input+no_connect"))
    )
    (net (code "70") (name "unconnected-(P1-Pad18)") (class "Default")
      (node (ref "P1") (pin "18") (pinfunction "18_18") (pintype "input+no_connect"))
    )
    (net (code "71") (name "unconnected-(P1-Pad19)") (class "Default")
      (node (ref "P1") (pin "19") (pinfunction "19_19") (pintype "input+no_connect"))
    )
    (net (code "72") (name "unconnected-(P1-Pad20)") (class "Default")
      (node (ref "P1") (pin "20") (pinfunction "20_20") (pintype "input+no_connect"))
    )
    (net (code "73") (name "unconnected-(P1-Pad21)") (class "Default")
      (node (ref "P1") (pin "21") (pinfunction "21_21") (pintype "input+no_connect"))
    )
    (net (code "74") (name "unconnected-(P1-Pad22)") (class "Default")
      (node (ref "P1") (pin "22") (pinfunction "22_22") (pintype "input+no_connect"))
    )
    (net (code "75") (name "unconnected-(P1-Pad23)") (class "Default")
      (node (ref "P1") (pin "23") (pinfunction "23_23") (pintype "input+no_connect"))
    )
    (net (code "76") (name "unconnected-(P1-Pad24)") (class "Default")
      (node (ref "P1") (pin "24") (pinfunction "24_24") (pintype "input+no_connect"))
    )
    (net (code "77") (name "unconnected-(P1-Pad25)") (class "Default")
      (node (ref "P1") (pin "25") (pinfunction "25_25") (pintype "input+no_connect"))
    )
    (net (code "78") (name "unconnected-(P1-Pad26)") (class "Default")
      (node (ref "P1") (pin "26") (pinfunction "26_26") (pintype "input+no_connect"))
    )
    (net (code "79") (name "unconnected-(P1-Pad27)") (class "Default")
      (node (ref "P1") (pin "27") (pinfunction "27_27") (pintype "input+no_connect"))
    )
    (net (code "80") (name "unconnected-(P1-Pad28)") (class "Default")
      (node (ref "P1") (pin "28") (pinfunction "28_28") (pintype "input+no_connect"))
    )
    (net (code "81") (name "unconnected-(P1-Pad29)") (class "Default")
      (node (ref "P1") (pin "29") (pinfunction "29_29") (pintype "input+no_connect"))
    )
    (net (code "82") (name "unconnected-(P1-Pad30)") (class "Default")
      (node (ref "P1") (pin "30") (pinfunction "30_30") (pintype "input+no_connect"))
    )
    (net (code "83") (name "unconnected-(P1-Pad31)") (class "Default")
      (node (ref "P1") (pin "31") (pinfunction "31_31") (pintype "input+no_connect"))
    )
    (net (code "84") (name "unconnected-(P1-Pad32)") (class "Default")
      (node (ref "P1") (pin "32") (pinfunction "32_32") (pintype "input+no_connect"))
    )
  )
)
